# mod_io.net
KiCad netlist of a schematic drawn in EAGLE
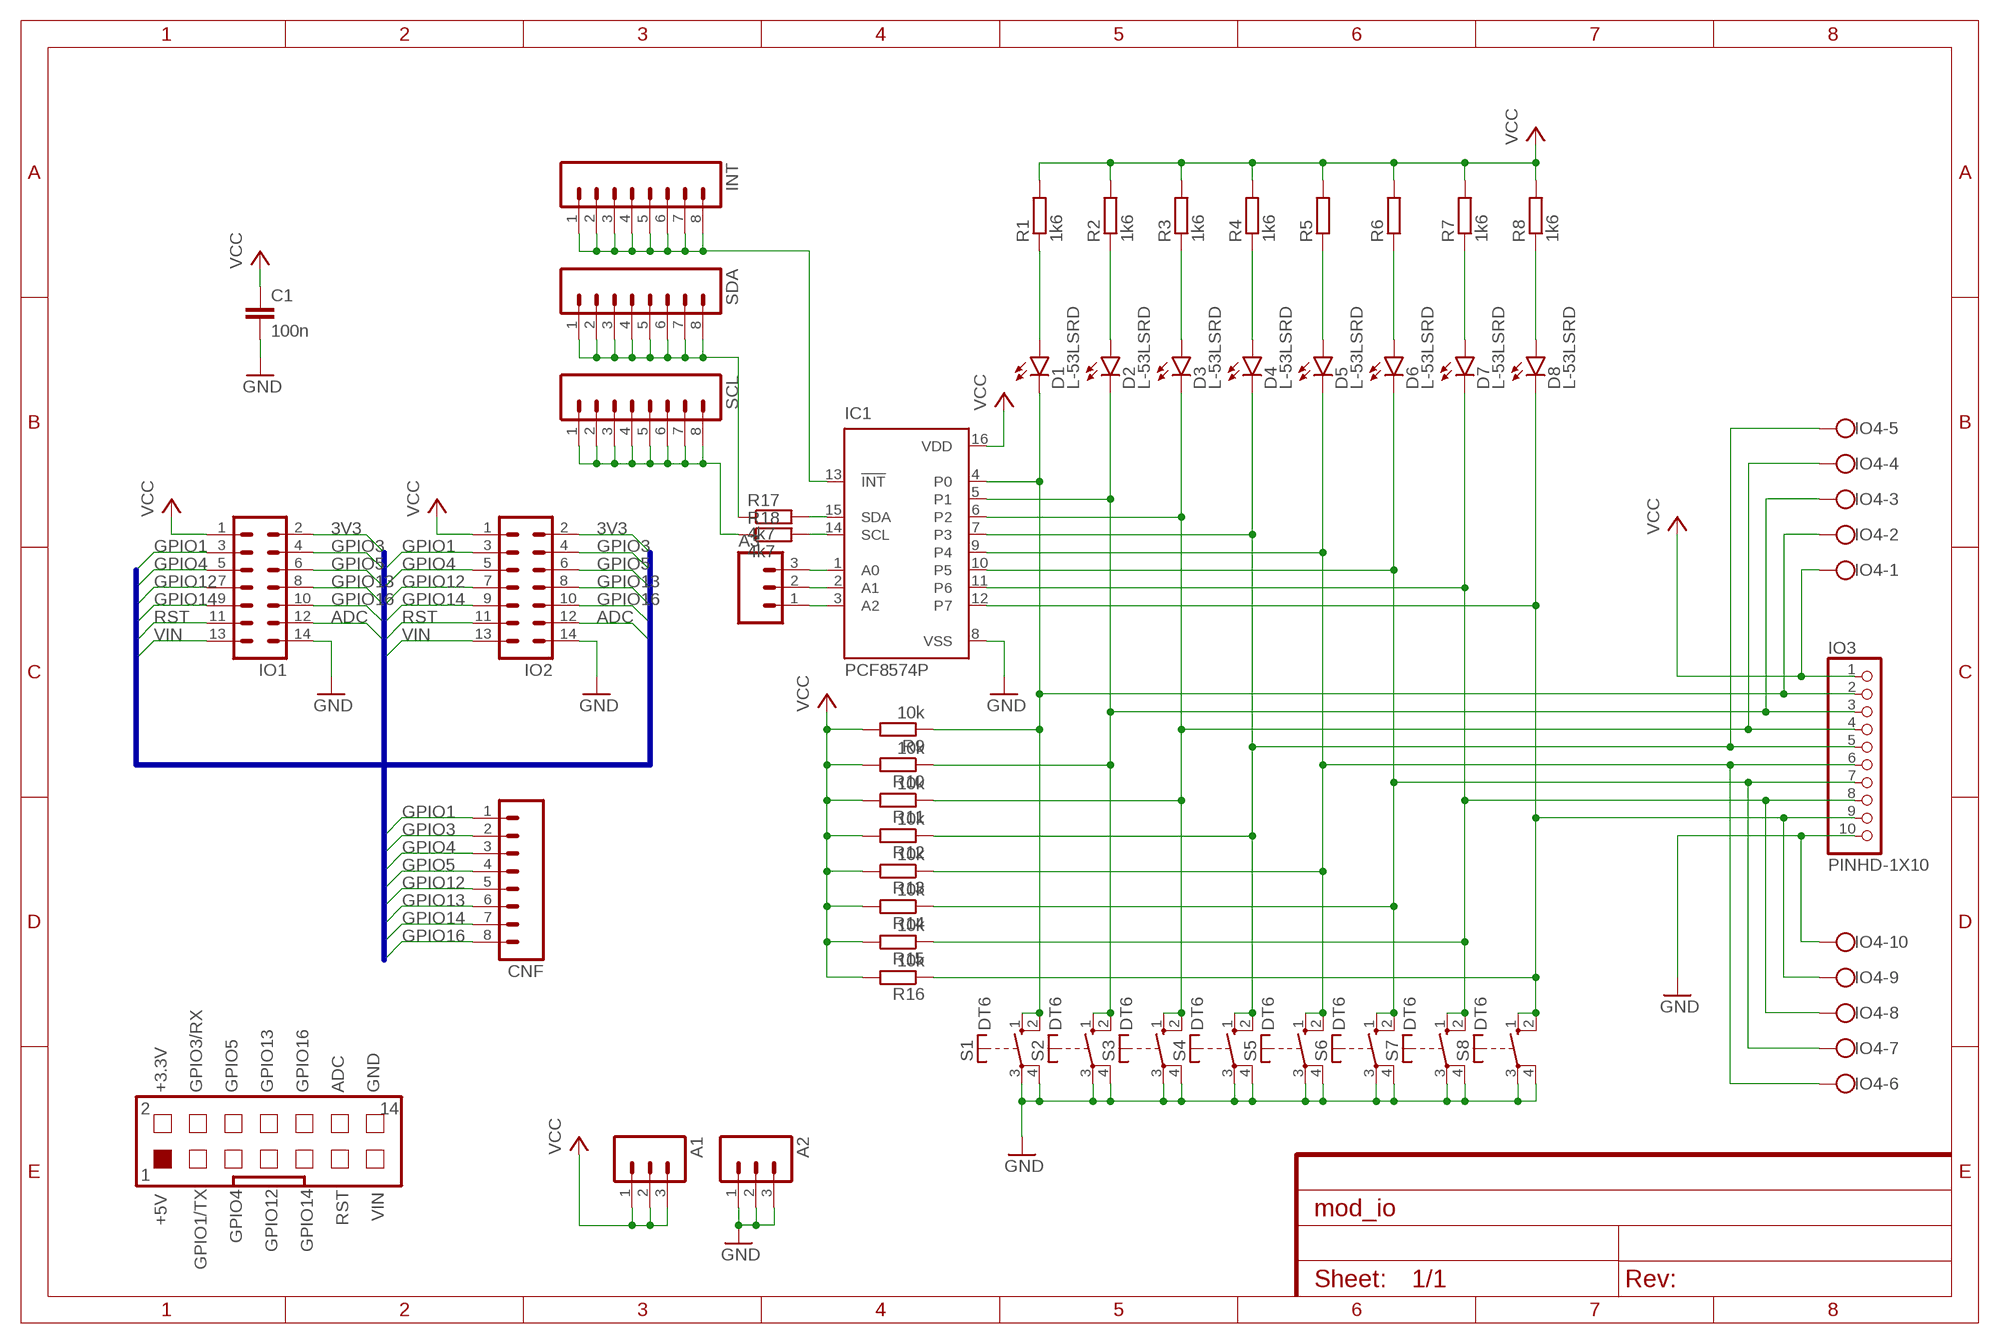
[diagram p0: schematic, sheet 1]

(export (version "E")
  (design (tool "Eeschema 10.0.6"))
  (components
    (comp (ref "A1")
      (value "M03LONGPADS")
      (footprint "eagle-import:1X03_LONGPADS")
      (libsource (lib "eagle-import") (part "M03LONGPADS"))
    )
    (comp (ref "A2")
      (value "M03LONGPADS")
      (footprint "eagle-import:1X03_LONGPADS")
      (libsource (lib "eagle-import") (part "M03LONGPADS"))
    )
    (comp (ref "A3")
      (value "M03LONGPADS")
      (footprint "eagle-import:1X03_LONGPADS")
      (libsource (lib "eagle-import") (part "M03LONGPADS"))
    )
    (comp (ref "C1")
      (value "100n")
      (footprint "eagle-import:C050-025X075")
      (libsource (lib "eagle-import") (part "C-EU050-025X075"))
    )
    (comp (ref "CNF")
      (value "M08LONGPADS")
      (footprint "eagle-import:1X08_LONGPADS")
      (libsource (lib "eagle-import") (part "M08LONGPADS"))
    )
    (comp (ref "D1")
      (value "L-53LSRD")
      (footprint "eagle-import:LED5MM")
      (libsource (lib "eagle-import") (part "LED5MM"))
    )
    (comp (ref "D2")
      (value "L-53LSRD")
      (footprint "eagle-import:LED5MM")
      (libsource (lib "eagle-import") (part "LED5MM"))
    )
    (comp (ref "D3")
      (value "L-53LSRD")
      (footprint "eagle-import:LED5MM")
      (libsource (lib "eagle-import") (part "LED5MM"))
    )
    (comp (ref "D4")
      (value "L-53LSRD")
      (footprint "eagle-import:LED5MM")
      (libsource (lib "eagle-import") (part "LED5MM"))
    )
    (comp (ref "D5")
      (value "L-53LSRD")
      (footprint "eagle-import:LED5MM")
      (libsource (lib "eagle-import") (part "LED5MM"))
    )
    (comp (ref "D6")
      (value "L-53LSRD")
      (footprint "eagle-import:LED5MM")
      (libsource (lib "eagle-import") (part "LED5MM"))
    )
    (comp (ref "D7")
      (value "L-53LSRD")
      (footprint "eagle-import:LED5MM")
      (libsource (lib "eagle-import") (part "LED5MM"))
    )
    (comp (ref "D8")
      (value "L-53LSRD")
      (footprint "eagle-import:LED5MM")
      (libsource (lib "eagle-import") (part "LED5MM"))
    )
    (comp (ref "IC1")
      (value "PCF8574P")
      (footprint "eagle-import:DIL16")
      (fields (field (name "MPN") "PCF8574PN"))
      (libsource (lib "eagle-import") (part "PCF8574P"))
    )
    (comp (ref "INT")
      (value "M08LONGPADS")
      (footprint "eagle-import:1X08_LONGPADS")
      (libsource (lib "eagle-import") (part "M08LONGPADS"))
    )
    (comp (ref "IO1")
      (value "14V")
      (footprint "eagle-import:14V")
      (libsource (lib "eagle-import") (part "14V"))
    )
    (comp (ref "IO2")
      (value "14V")
      (footprint "eagle-import:14V")
      (libsource (lib "eagle-import") (part "14V"))
    )
    (comp (ref "IO3")
      (value "PINHD-1X10")
      (footprint "eagle-import:1X10-BIG")
      (libsource (lib "eagle-import") (part "PINHD-1X10"))
    )
    (comp (ref "IO4")
      (value "AK550/10")
      (footprint "eagle-import:AK550_10")
      (libsource (lib "eagle-import") (part "AK550/10"))
    )
    (comp (ref "R1")
      (value "1k6")
      (footprint "eagle-import:0207_10")
      (libsource (lib "eagle-import") (part "R-EU_0207/10"))
    )
    (comp (ref "R2")
      (value "1k6")
      (footprint "eagle-import:0207_10")
      (libsource (lib "eagle-import") (part "R-EU_0207/10"))
    )
    (comp (ref "R3")
      (value "1k6")
      (footprint "eagle-import:0207_10")
      (libsource (lib "eagle-import") (part "R-EU_0207/10"))
    )
    (comp (ref "R4")
      (value "1k6")
      (footprint "eagle-import:0207_10")
      (libsource (lib "eagle-import") (part "R-EU_0207/10"))
    )
    (comp (ref "R5")
      (value "R-EU_0207/10")
      (footprint "eagle-import:0207_10")
      (libsource (lib "eagle-import") (part "R-EU_0207/10"))
    )
    (comp (ref "R6")
      (value "R-EU_0207/10")
      (footprint "eagle-import:0207_10")
      (libsource (lib "eagle-import") (part "R-EU_0207/10"))
    )
    (comp (ref "R7")
      (value "1k6")
      (footprint "eagle-import:0207_10")
      (libsource (lib "eagle-import") (part "R-EU_0207/10"))
    )
    (comp (ref "R8")
      (value "1k6")
      (footprint "eagle-import:0207_10")
      (libsource (lib "eagle-import") (part "R-EU_0207/10"))
    )
    (comp (ref "R9")
      (value "10k")
      (footprint "eagle-import:0207_10")
      (libsource (lib "eagle-import") (part "R-EU_0207/10"))
    )
    (comp (ref "R10")
      (value "10k")
      (footprint "eagle-import:0207_10")
      (libsource (lib "eagle-import") (part "R-EU_0207/10"))
    )
    (comp (ref "R11")
      (value "10k")
      (footprint "eagle-import:0207_10")
      (libsource (lib "eagle-import") (part "R-EU_0207/10"))
    )
    (comp (ref "R12")
      (value "10k")
      (footprint "eagle-import:0207_10")
      (libsource (lib "eagle-import") (part "R-EU_0207/10"))
    )
    (comp (ref "R13")
      (value "10k")
      (footprint "eagle-import:0207_10")
      (libsource (lib "eagle-import") (part "R-EU_0207/10"))
    )
    (comp (ref "R14")
      (value "10k")
      (footprint "eagle-import:0207_10")
      (libsource (lib "eagle-import") (part "R-EU_0207/10"))
    )
    (comp (ref "R15")
      (value "10k")
      (footprint "eagle-import:0207_10")
      (libsource (lib "eagle-import") (part "R-EU_0207/10"))
    )
    (comp (ref "R16")
      (value "10k")
      (footprint "eagle-import:0207_10")
      (libsource (lib "eagle-import") (part "R-EU_0207/10"))
    )
    (comp (ref "R17")
      (value "4k7")
      (footprint "eagle-import:0207_10")
      (libsource (lib "eagle-import") (part "R-EU_0207/10"))
    )
    (comp (ref "R18")
      (value "4k7")
      (footprint "eagle-import:0207_10")
      (libsource (lib "eagle-import") (part "R-EU_0207/10"))
    )
    (comp (ref "S1")
      (value "DT6")
      (footprint "eagle-import:DT6")
      (libsource (lib "eagle-import") (part "DT6"))
    )
    (comp (ref "S2")
      (value "DT6")
      (footprint "eagle-import:DT6")
      (libsource (lib "eagle-import") (part "DT6"))
    )
    (comp (ref "S3")
      (value "DT6")
      (footprint "eagle-import:DT6")
      (libsource (lib "eagle-import") (part "DT6"))
    )
    (comp (ref "S4")
      (value "DT6")
      (footprint "eagle-import:DT6")
      (libsource (lib "eagle-import") (part "DT6"))
    )
    (comp (ref "S5")
      (value "DT6")
      (footprint "eagle-import:DT6")
      (libsource (lib "eagle-import") (part "DT6"))
    )
    (comp (ref "S6")
      (value "DT6")
      (footprint "eagle-import:DT6")
      (libsource (lib "eagle-import") (part "DT6"))
    )
    (comp (ref "S7")
      (value "DT6")
      (footprint "eagle-import:DT6")
      (libsource (lib "eagle-import") (part "DT6"))
    )
    (comp (ref "S8")
      (value "DT6")
      (footprint "eagle-import:DT6")
      (libsource (lib "eagle-import") (part "DT6"))
    )
    (comp (ref "SCL")
      (value "M08LONGPADS")
      (footprint "eagle-import:1X08_LONGPADS")
      (libsource (lib "eagle-import") (part "M08LONGPADS"))
    )
    (comp (ref "SDA")
      (value "M08LONGPADS")
      (footprint "eagle-import:1X08_LONGPADS")
      (libsource (lib "eagle-import") (part "M08LONGPADS"))
    )
  )
  (nets
    (net (code "1") (name "/3V3") (class "Default")
      (node (ref "IO1") (pin "2") (pinfunction "2_2") (pintype "passive"))
      (node (ref "IO2") (pin "2") (pinfunction "2_2") (pintype "passive"))
    )
    (net (code "2") (name "/ADC") (class "Default")
      (node (ref "IO1") (pin "12") (pinfunction "12_12") (pintype "passive"))
      (node (ref "IO2") (pin "12") (pinfunction "12_12") (pintype "passive"))
    )
    (net (code "3") (name "/GPIO1") (class "Default")
      (node (ref "CNF") (pin "1") (pinfunction "1_1") (pintype "passive"))
      (node (ref "IO1") (pin "3") (pinfunction "3_3") (pintype "passive"))
      (node (ref "IO2") (pin "3") (pinfunction "3_3") (pintype "passive"))
    )
    (net (code "4") (name "/GPIO3") (class "Default")
      (node (ref "CNF") (pin "2") (pinfunction "2_2") (pintype "passive"))
      (node (ref "IO1") (pin "4") (pinfunction "4_4") (pintype "passive"))
      (node (ref "IO2") (pin "4") (pinfunction "4_4") (pintype "passive"))
    )
    (net (code "5") (name "/GPIO4") (class "Default")
      (node (ref "CNF") (pin "3") (pinfunction "3_3") (pintype "passive"))
      (node (ref "IO1") (pin "5") (pinfunction "5_5") (pintype "passive"))
      (node (ref "IO2") (pin "5") (pinfunction "5_5") (pintype "passive"))
    )
    (net (code "6") (name "/GPIO5") (class "Default")
      (node (ref "CNF") (pin "4") (pinfunction "4_4") (pintype "passive"))
      (node (ref "IO1") (pin "6") (pinfunction "6_6") (pintype "passive"))
      (node (ref "IO2") (pin "6") (pinfunction "6_6") (pintype "passive"))
    )
    (net (code "7") (name "/GPIO12") (class "Default")
      (node (ref "CNF") (pin "5") (pinfunction "5_5") (pintype "passive"))
      (node (ref "IO1") (pin "7") (pinfunction "7_7") (pintype "passive"))
      (node (ref "IO2") (pin "7") (pinfunction "7_7") (pintype "passive"))
    )
    (net (code "8") (name "/GPIO13") (class "Default")
      (node (ref "CNF") (pin "6") (pinfunction "6_6") (pintype "passive"))
      (node (ref "IO1") (pin "8") (pinfunction "8_8") (pintype "passive"))
      (node (ref "IO2") (pin "8") (pinfunction "8_8") (pintype "passive"))
    )
    (net (code "9") (name "/GPIO14") (class "Default")
      (node (ref "CNF") (pin "7") (pinfunction "7_7") (pintype "passive"))
      (node (ref "IO1") (pin "9") (pinfunction "9_9") (pintype "passive"))
      (node (ref "IO2") (pin "9") (pinfunction "9_9") (pintype "passive"))
    )
    (net (code "10") (name "/GPIO16") (class "Default")
      (node (ref "CNF") (pin "8") (pinfunction "8_8") (pintype "passive"))
      (node (ref "IO1") (pin "10") (pinfunction "10_10") (pintype "passive"))
      (node (ref "IO2") (pin "10") (pinfunction "10_10") (pintype "passive"))
    )
    (net (code "11") (name "/RST") (class "Default")
      (node (ref "IO1") (pin "11") (pinfunction "11_11") (pintype "passive"))
      (node (ref "IO2") (pin "11") (pinfunction "11_11") (pintype "passive"))
    )
    (net (code "12") (name "/VIN") (class "Default")
      (node (ref "IO1") (pin "13") (pinfunction "13_13") (pintype "passive"))
      (node (ref "IO2") (pin "13") (pinfunction "13_13") (pintype "passive"))
    )
    (net (code "13") (name "GND") (class "Default")
      (node (ref "A2") (pin "1") (pinfunction "1_1") (pintype "passive"))
      (node (ref "A2") (pin "2") (pinfunction "2_2") (pintype "passive"))
      (node (ref "A2") (pin "3") (pinfunction "3_3") (pintype "passive"))
      (node (ref "C1") (pin "2") (pinfunction "2_2") (pintype "passive"))
      (node (ref "IC1") (pin "8") (pinfunction "VSS_8") (pintype "power_in"))
      (node (ref "IO1") (pin "14") (pinfunction "14_14") (pintype "passive"))
      (node (ref "IO2") (pin "14") (pinfunction "14_14") (pintype "passive"))
      (node (ref "IO3") (pin "10") (pinfunction "10_10") (pintype "passive"))
      (node (ref "IO4") (pin "10") (pinfunction "KL_10") (pintype "passive"))
      (node (ref "S1") (pin "3") (pinfunction "P_3") (pintype "passive"))
      (node (ref "S1") (pin "4") (pinfunction "P_4") (pintype "passive"))
      (node (ref "S2") (pin "3") (pinfunction "P_3") (pintype "passive"))
      (node (ref "S2") (pin "4") (pinfunction "P_4") (pintype "passive"))
      (node (ref "S3") (pin "3") (pinfunction "P_3") (pintype "passive"))
      (node (ref "S3") (pin "4") (pinfunction "P_4") (pintype "passive"))
      (node (ref "S4") (pin "3") (pinfunction "P_3") (pintype "passive"))
      (node (ref "S4") (pin "4") (pinfunction "P_4") (pintype "passive"))
      (node (ref "S5") (pin "3") (pinfunction "P_3") (pintype "passive"))
      (node (ref "S5") (pin "4") (pinfunction "P_4") (pintype "passive"))
      (node (ref "S6") (pin "3") (pinfunction "P_3") (pintype "passive"))
      (node (ref "S6") (pin "4") (pinfunction "P_4") (pintype "passive"))
      (node (ref "S7") (pin "3") (pinfunction "P_3") (pintype "passive"))
      (node (ref "S7") (pin "4") (pinfunction "P_4") (pintype "passive"))
      (node (ref "S8") (pin "3") (pinfunction "P_3") (pintype "passive"))
      (node (ref "S8") (pin "4") (pinfunction "P_4") (pintype "passive"))
    )
    (net (code "14") (name "Net-(D1-C)") (class "Default")
      (node (ref "D1") (pin "K") (pinfunction "C_K") (pintype "passive"))
      (node (ref "IC1") (pin "4") (pinfunction "P0_4") (pintype "bidirectional"))
      (node (ref "IO3") (pin "2") (pinfunction "2_2") (pintype "passive"))
      (node (ref "IO4") (pin "2") (pinfunction "KL_2") (pintype "passive"))
      (node (ref "R9") (pin "1") (pinfunction "1_1") (pintype "passive"))
      (node (ref "S1") (pin "1") (pinfunction "S_1") (pintype "passive"))
      (node (ref "S1") (pin "2") (pinfunction "S_2") (pintype "passive"))
    )
    (net (code "15") (name "Net-(D1-PadA)") (class "Default")
      (node (ref "D1") (pin "A") (pinfunction "A_A") (pintype "passive"))
      (node (ref "R1") (pin "1") (pinfunction "1_1") (pintype "passive"))
    )
    (net (code "16") (name "Net-(D2-C)") (class "Default")
      (node (ref "D2") (pin "K") (pinfunction "C_K") (pintype "passive"))
      (node (ref "IC1") (pin "5") (pinfunction "P1_5") (pintype "bidirectional"))
      (node (ref "IO3") (pin "3") (pinfunction "3_3") (pintype "passive"))
      (node (ref "IO4") (pin "3") (pinfunction "KL_3") (pintype "passive"))
      (node (ref "R10") (pin "1") (pinfunction "1_1") (pintype "passive"))
      (node (ref "S2") (pin "1") (pinfunction "S_1") (pintype "passive"))
      (node (ref "S2") (pin "2") (pinfunction "S_2") (pintype "passive"))
    )
    (net (code "17") (name "Net-(D2-PadA)") (class "Default")
      (node (ref "D2") (pin "A") (pinfunction "A_A") (pintype "passive"))
      (node (ref "R2") (pin "1") (pinfunction "1_1") (pintype "passive"))
    )
    (net (code "18") (name "Net-(D3-C)") (class "Default")
      (node (ref "D3") (pin "K") (pinfunction "C_K") (pintype "passive"))
      (node (ref "IC1") (pin "6") (pinfunction "P2_6") (pintype "bidirectional"))
      (node (ref "IO3") (pin "4") (pinfunction "4_4") (pintype "passive"))
      (node (ref "IO4") (pin "4") (pinfunction "KL_4") (pintype "passive"))
      (node (ref "R11") (pin "1") (pinfunction "1_1") (pintype "passive"))
      (node (ref "S3") (pin "1") (pinfunction "S_1") (pintype "passive"))
      (node (ref "S3") (pin "2") (pinfunction "S_2") (pintype "passive"))
    )
    (net (code "19") (name "Net-(D3-PadA)") (class "Default")
      (node (ref "D3") (pin "A") (pinfunction "A_A") (pintype "passive"))
      (node (ref "R3") (pin "1") (pinfunction "1_1") (pintype "passive"))
    )
    (net (code "20") (name "Net-(D4-C)") (class "Default")
      (node (ref "D4") (pin "K") (pinfunction "C_K") (pintype "passive"))
      (node (ref "IC1") (pin "7") (pinfunction "P3_7") (pintype "bidirectional"))
      (node (ref "IO3") (pin "5") (pinfunction "5_5") (pintype "passive"))
      (node (ref "IO4") (pin "5") (pinfunction "KL_5") (pintype "passive"))
      (node (ref "R12") (pin "1") (pinfunction "1_1") (pintype "passive"))
      (node (ref "S4") (pin "1") (pinfunction "S_1") (pintype "passive"))
      (node (ref "S4") (pin "2") (pinfunction "S_2") (pintype "passive"))
    )
    (net (code "21") (name "Net-(D4-PadA)") (class "Default")
      (node (ref "D4") (pin "A") (pinfunction "A_A") (pintype "passive"))
      (node (ref "R4") (pin "1") (pinfunction "1_1") (pintype "passive"))
    )
    (net (code "22") (name "Net-(D5-C)") (class "Default")
      (node (ref "D5") (pin "K") (pinfunction "C_K") (pintype "passive"))
      (node (ref "IC1") (pin "9") (pinfunction "P4_9") (pintype "bidirectional"))
      (node (ref "IO3") (pin "6") (pinfunction "6_6") (pintype "passive"))
      (node (ref "IO4") (pin "6") (pinfunction "KL_6") (pintype "passive"))
      (node (ref "R13") (pin "1") (pinfunction "1_1") (pintype "passive"))
      (node (ref "S5") (pin "1") (pinfunction "S_1") (pintype "passive"))
      (node (ref "S5") (pin "2") (pinfunction "S_2") (pintype "passive"))
    )
    (net (code "23") (name "Net-(D5-PadA)") (class "Default")
      (node (ref "D5") (pin "A") (pinfunction "A_A") (pintype "passive"))
      (node (ref "R5") (pin "1") (pinfunction "1_1") (pintype "passive"))
    )
    (net (code "24") (name "Net-(D6-C)") (class "Default")
      (node (ref "D6") (pin "K") (pinfunction "C_K") (pintype "passive"))
      (node (ref "IC1") (pin "10") (pinfunction "P5_10") (pintype "bidirectional"))
      (node (ref "IO3") (pin "7") (pinfunction "7_7") (pintype "passive"))
      (node (ref "IO4") (pin "7") (pinfunction "KL_7") (pintype "passive"))
      (node (ref "R14") (pin "1") (pinfunction "1_1") (pintype "passive"))
      (node (ref "S6") (pin "1") (pinfunction "S_1") (pintype "passive"))
      (node (ref "S6") (pin "2") (pinfunction "S_2") (pintype "passive"))
    )
    (net (code "25") (name "Net-(D6-PadA)") (class "Default")
      (node (ref "D6") (pin "A") (pinfunction "A_A") (pintype "passive"))
      (node (ref "R6") (pin "1") (pinfunction "1_1") (pintype "passive"))
    )
    (net (code "26") (name "Net-(D7-C)") (class "Default")
      (node (ref "D7") (pin "K") (pinfunction "C_K") (pintype "passive"))
      (node (ref "IC1") (pin "11") (pinfunction "P6_11") (pintype "bidirectional"))
      (node (ref "IO3") (pin "8") (pinfunction "8_8") (pintype "passive"))
      (node (ref "IO4") (pin "8") (pinfunction "KL_8") (pintype "passive"))
      (node (ref "R15") (pin "1") (pinfunction "1_1") (pintype "passive"))
      (node (ref "S7") (pin "1") (pinfunction "S_1") (pintype "passive"))
      (node (ref "S7") (pin "2") (pinfunction "S_2") (pintype "passive"))
    )
    (net (code "27") (name "Net-(D7-PadA)") (class "Default")
      (node (ref "D7") (pin "A") (pinfunction "A_A") (pintype "passive"))
      (node (ref "R7") (pin "1") (pinfunction "1_1") (pintype "passive"))
    )
    (net (code "28") (name "Net-(D8-C)") (class "Default")
      (node (ref "D8") (pin "K") (pinfunction "C_K") (pintype "passive"))
      (node (ref "IC1") (pin "12") (pinfunction "P7_12") (pintype "bidirectional"))
      (node (ref "IO3") (pin "9") (pinfunction "9_9") (pintype "passive"))
      (node (ref "IO4") (pin "9") (pinfunction "KL_9") (pintype "passive"))
      (node (ref "R16") (pin "1") (pinfunction "1_1") (pintype "passive"))
      (node (ref "S8") (pin "1") (pinfunction "S_1") (pintype "passive"))
      (node (ref "S8") (pin "2") (pinfunction "S_2") (pintype "passive"))
    )
    (net (code "29") (name "Net-(D8-PadA)") (class "Default")
      (node (ref "D8") (pin "A") (pinfunction "A_A") (pintype "passive"))
      (node (ref "R8") (pin "1") (pinfunction "1_1") (pintype "passive"))
    )
    (net (code "30") (name "Net-(IC1-A0)") (class "Default")
      (node (ref "A3") (pin "3") (pinfunction "3_3") (pintype "passive"))
      (node (ref "IC1") (pin "1") (pinfunction "A0_1") (pintype "input"))
    )
    (net (code "31") (name "Net-(IC1-A1)") (class "Default")
      (node (ref "A3") (pin "2") (pinfunction "2_2") (pintype "passive"))
      (node (ref "IC1") (pin "2") (pinfunction "A1_2") (pintype "input"))
    )
    (net (code "32") (name "Net-(IC1-A2)") (class "Default")
      (node (ref "A3") (pin "1") (pinfunction "1_1") (pintype "passive"))
      (node (ref "IC1") (pin "3") (pinfunction "A2_3") (pintype "input"))
    )
    (net (code "33") (name "Net-(IC1-SCL)") (class "Default")
      (node (ref "IC1") (pin "14") (pinfunction "SCL_14") (pintype "input"))
      (node (ref "R18") (pin "2") (pinfunction "2_2") (pintype "passive"))
    )
    (net (code "34") (name "Net-(IC1-SDA)") (class "Default")
      (node (ref "IC1") (pin "15") (pinfunction "SDA_15") (pintype "bidirectional"))
      (node (ref "R17") (pin "2") (pinfunction "2_2") (pintype "passive"))
    )
    (net (code "35") (name "Net-(IC1-~{INT})") (class "Default")
      (node (ref "IC1") (pin "13") (pinfunction "~{INT}_13") (pintype "output"))
      (node (ref "INT") (pin "1") (pinfunction "1_1") (pintype "passive"))
      (node (ref "INT") (pin "2") (pinfunction "2_2") (pintype "passive"))
      (node (ref "INT") (pin "3") (pinfunction "3_3") (pintype "passive"))
      (node (ref "INT") (pin "4") (pinfunction "4_4") (pintype "passive"))
      (node (ref "INT") (pin "5") (pinfunction "5_5") (pintype "passive"))
      (node (ref "INT") (pin "6") (pinfunction "6_6") (pintype "passive"))
      (node (ref "INT") (pin "7") (pinfunction "7_7") (pintype "passive"))
      (node (ref "INT") (pin "8") (pinfunction "8_8") (pintype "passive"))
    )
    (net (code "36") (name "Net-(R17-Pad1)") (class "Default")
      (node (ref "R17") (pin "1") (pinfunction "1_1") (pintype "passive"))
      (node (ref "SDA") (pin "1") (pinfunction "1_1") (pintype "passive"))
      (node (ref "SDA") (pin "2") (pinfunction "2_2") (pintype "passive"))
      (node (ref "SDA") (pin "3") (pinfunction "3_3") (pintype "passive"))
      (node (ref "SDA") (pin "4") (pinfunction "4_4") (pintype "passive"))
      (node (ref "SDA") (pin "5") (pinfunction "5_5") (pintype "passive"))
      (node (ref "SDA") (pin "6") (pinfunction "6_6") (pintype "passive"))
      (node (ref "SDA") (pin "7") (pinfunction "7_7") (pintype "passive"))
      (node (ref "SDA") (pin "8") (pinfunction "8_8") (pintype "passive"))
    )
    (net (code "37") (name "Net-(R18-Pad1)") (class "Default")
      (node (ref "R18") (pin "1") (pinfunction "1_1") (pintype "passive"))
      (node (ref "SCL") (pin "1") (pinfunction "1_1") (pintype "passive"))
      (node (ref "SCL") (pin "2") (pinfunction "2_2") (pintype "passive"))
      (node (ref "SCL") (pin "3") (pinfunction "3_3") (pintype "passive"))
      (node (ref "SCL") (pin "4") (pinfunction "4_4") (pintype "passive"))
      (node (ref "SCL") (pin "5") (pinfunction "5_5") (pintype "passive"))
      (node (ref "SCL") (pin "6") (pinfunction "6_6") (pintype "passive"))
      (node (ref "SCL") (pin "7") (pinfunction "7_7") (pintype "passive"))
      (node (ref "SCL") (pin "8") (pinfunction "8_8") (pintype "passive"))
    )
    (net (code "38") (name "VCC") (class "Default")
      (node (ref "A1") (pin "1") (pinfunction "1_1") (pintype "passive"))
      (node (ref "A1") (pin "2") (pinfunction "2_2") (pintype "passive"))
      (node (ref "A1") (pin "3") (pinfunction "3_3") (pintype "passive"))
      (node (ref "C1") (pin "1") (pinfunction "1_1") (pintype "passive"))
      (node (ref "IC1") (pin "16") (pinfunction "VDD_16") (pintype "power_in"))
      (node (ref "IO1") (pin "1") (pinfunction "1_1") (pintype "passive"))
      (node (ref "IO2") (pin "1") (pinfunction "1_1") (pintype "passive"))
      (node (ref "IO3") (pin "1") (pinfunction "1_1") (pintype "passive"))
      (node (ref "IO4") (pin "1") (pinfunction "KL_1") (pintype "passive"))
      (node (ref "R1") (pin "2") (pinfunction "2_2") (pintype "passive"))
      (node (ref "R10") (pin "2") (pinfunction "2_2") (pintype "passive"))
      (node (ref "R11") (pin "2") (pinfunction "2_2") (pintype "passive"))
      (node (ref "R12") (pin "2") (pinfunction "2_2") (pintype "passive"))
      (node (ref "R13") (pin "2") (pinfunction "2_2") (pintype "passive"))
      (node (ref "R14") (pin "2") (pinfunction "2_2") (pintype "passive"))
      (node (ref "R15") (pin "2") (pinfunction "2_2") (pintype "passive"))
      (node (ref "R16") (pin "2") (pinfunction "2_2") (pintype "passive"))
      (node (ref "R2") (pin "2") (pinfunction "2_2") (pintype "passive"))
      (node (ref "R3") (pin "2") (pinfunction "2_2") (pintype "passive"))
      (node (ref "R4") (pin "2") (pinfunction "2_2") (pintype "passive"))
      (node (ref "R5") (pin "2") (pinfunction "2_2") (pintype "passive"))
      (node (ref "R6") (pin "2") (pinfunction "2_2") (pintype "passive"))
      (node (ref "R7") (pin "2") (pinfunction "2_2") (pintype "passive"))
      (node (ref "R8") (pin "2") (pinfunction "2_2") (pintype "passive"))
      (node (ref "R9") (pin "2") (pinfunction "2_2") (pintype "passive"))
    )
  )
)
